# USB_PD.net
KiCad netlist of a schematic drawn in Altium Designer
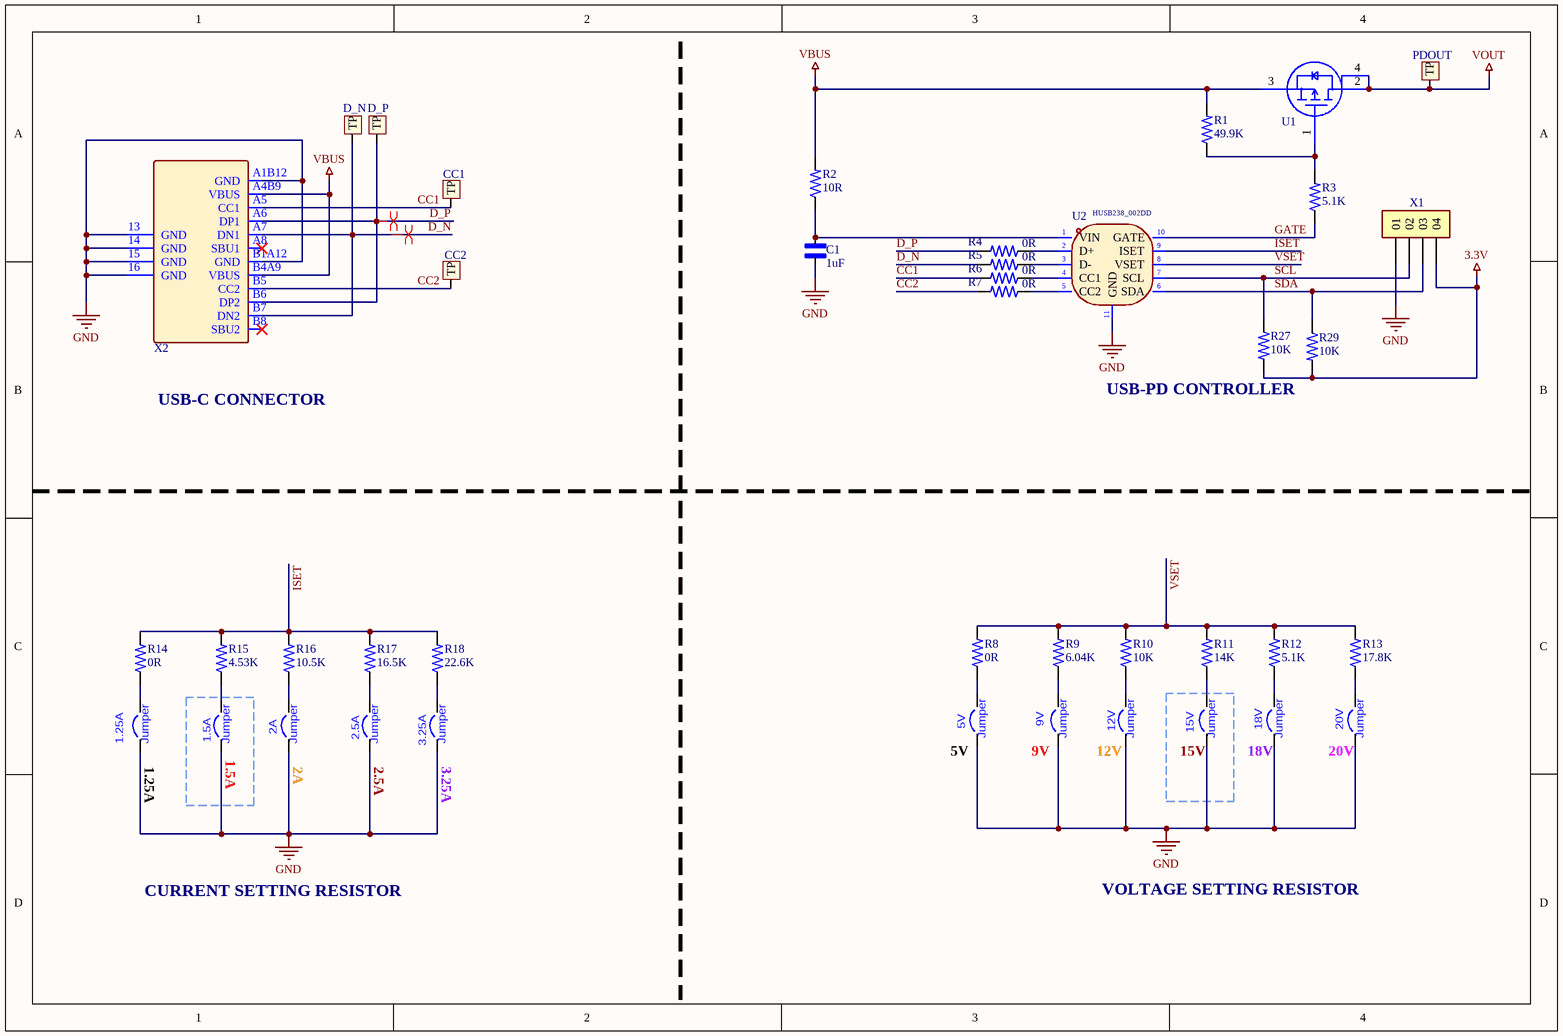
[diagram p0: USB_PD.SchDoc]

(export (version "E")
  (design (tool "Eeschema 10.0.6"))
  (components
    (comp (ref "1.5A")
      (value "Jumper")
      (footprint "PAD-JUMPER-2-NC_BY_PASTE_YES_SILK")
      (description "SMD JUMPER")
      (libsource (lib "USB_PD_DVD") (part "JUMPER SOLDER BRIDGE"))
    )
    (comp (ref "1.25A")
      (value "Jumper")
      (footprint "PAD-JUMPER-2-NC_BY_PASTE_YES_SILK")
      (description "SMD JUMPER")
      (libsource (lib "USB_PD_DVD") (part "JUMPER SOLDER BRIDGE"))
    )
    (comp (ref "2.5A")
      (value "Jumper")
      (footprint "PAD-JUMPER-2-NC_BY_PASTE_YES_SILK")
      (description "SMD JUMPER")
      (libsource (lib "USB_PD_DVD") (part "JUMPER SOLDER BRIDGE"))
    )
    (comp (ref "2A")
      (value "Jumper")
      (footprint "PAD-JUMPER-2-NC_BY_PASTE_YES_SILK")
      (description "SMD JUMPER")
      (libsource (lib "USB_PD_DVD") (part "JUMPER SOLDER BRIDGE"))
    )
    (comp (ref "3.25A")
      (value "Jumper")
      (footprint "PAD-JUMPER-2-NC_BY_PASTE_YES_SILK")
      (description "SMD JUMPER")
      (libsource (lib "USB_PD_DVD") (part "JUMPER SOLDER BRIDGE"))
    )
    (comp (ref "5V")
      (value "Jumper")
      (footprint "PAD-JUMPER-2-NC_BY_PASTE_YES_SILK")
      (description "SMD JUMPER")
      (libsource (lib "USB_PD_DVD") (part "JUMPER SOLDER BRIDGE"))
    )
    (comp (ref "9V")
      (value "Jumper")
      (footprint "PAD-JUMPER-2-NC_BY_PASTE_YES_SILK")
      (description "SMD JUMPER")
      (libsource (lib "USB_PD_DVD") (part "JUMPER SOLDER BRIDGE"))
    )
    (comp (ref "12V")
      (value "Jumper")
      (footprint "PAD-JUMPER-2-NC_BY_PASTE_YES_SILK")
      (description "SMD JUMPER")
      (libsource (lib "USB_PD_DVD") (part "JUMPER SOLDER BRIDGE"))
    )
    (comp (ref "15V")
      (value "Jumper")
      (footprint "PAD-JUMPER-2-NC_BY_PASTE_YES_SILK")
      (description "SMD JUMPER")
      (libsource (lib "USB_PD_DVD") (part "JUMPER SOLDER BRIDGE"))
    )
    (comp (ref "18V")
      (value "Jumper")
      (footprint "PAD-JUMPER-2-NC_BY_PASTE_YES_SILK")
      (description "SMD JUMPER")
      (libsource (lib "USB_PD_DVD") (part "JUMPER SOLDER BRIDGE"))
    )
    (comp (ref "20V")
      (value "Jumper")
      (footprint "PAD-JUMPER-2-NC_BY_PASTE_YES_SILK")
      (description "SMD JUMPER")
      (libsource (lib "USB_PD_DVD") (part "JUMPER SOLDER BRIDGE"))
    )
    (comp (ref "C1")
      (value "1uF")
      (footprint "CAP 0402")
      (fields
        (field (name "VOLTAGE") "50V")
        (field (name "TOLERANCE") "±10%")
        (field (name "Comment") "SMD capacitor")
      )
      (libsource (lib "USB_PD_DVD") (part "CAP_SMD_CERAMIC"))
    )
    (comp (ref "CC1")
      (value "TEST POINT")
      (footprint "TESTPOINT")
      (libsource (lib "USB_PD_DVD") (part "TEST POINT"))
    )
    (comp (ref "CC2")
      (value "TEST POINT")
      (footprint "TESTPOINT")
      (libsource (lib "USB_PD_DVD") (part "TEST POINT"))
    )
    (comp (ref "D_N")
      (value "TEST POINT")
      (footprint "TESTPOINT")
      (libsource (lib "USB_PD_DVD") (part "TEST POINT"))
    )
    (comp (ref "D_P")
      (value "TEST POINT")
      (footprint "TESTPOINT")
      (libsource (lib "USB_PD_DVD") (part "TEST POINT"))
    )
    (comp (ref "PDOUT")
      (value "TEST POINT")
      (footprint "TESTPOINT")
      (libsource (lib "USB_PD_DVD") (part "TEST POINT"))
    )
    (comp (ref "R1")
      (value "49.9K")
      (footprint "RES_0603")
      (fields (field (name "TOLERANCE") "±5%") (field (name "Comment") "SMD resistor"))
      (libsource (lib "USB_PD_DVD") (part "RES_SMD_CERAMIC"))
    )
    (comp (ref "R2")
      (value "10R")
      (footprint "RES_0603")
      (fields (field (name "TOLERANCE") "±5%") (field (name "Comment") "SMD resistor"))
      (libsource (lib "USB_PD_DVD") (part "RES_SMD_CERAMIC"))
    )
    (comp (ref "R3")
      (value "5.1K")
      (footprint "RES_0603")
      (fields (field (name "TOLERANCE") "±5%") (field (name "Comment") "SMD resistor"))
      (libsource (lib "USB_PD_DVD") (part "RES_SMD_CERAMIC"))
    )
    (comp (ref "R4")
      (value "0R")
      (footprint "RES 0402")
      (fields (field (name "TOLERANCE") "±5%") (field (name "Comment") "SMD resistor"))
      (libsource (lib "USB_PD_DVD") (part "RES_SMD_CERAMIC"))
    )
    (comp (ref "R5")
      (value "0R")
      (footprint "RES 0402")
      (fields (field (name "TOLERANCE") "±5%") (field (name "Comment") "SMD resistor"))
      (libsource (lib "USB_PD_DVD") (part "RES_SMD_CERAMIC"))
    )
    (comp (ref "R6")
      (value "0R")
      (footprint "RES 0402")
      (fields (field (name "TOLERANCE") "±5%") (field (name "Comment") "SMD resistor"))
      (libsource (lib "USB_PD_DVD") (part "RES_SMD_CERAMIC"))
    )
    (comp (ref "R7")
      (value "0R")
      (footprint "RES 0402")
      (fields (field (name "TOLERANCE") "±5%") (field (name "Comment") "SMD resistor"))
      (libsource (lib "USB_PD_DVD") (part "RES_SMD_CERAMIC"))
    )
    (comp (ref "R8")
      (value "0R")
      (footprint "RES 0402")
      (fields (field (name "TOLERANCE") "±5%") (field (name "Comment") "SMD resistor"))
      (libsource (lib "USB_PD_DVD") (part "RES_SMD_CERAMIC"))
    )
    (comp (ref "R9")
      (value "6.04K")
      (footprint "RES 0402")
      (fields (field (name "TOLERANCE") "±5%") (field (name "Comment") "SMD resistor"))
      (libsource (lib "USB_PD_DVD") (part "RES_SMD_CERAMIC"))
    )
    (comp (ref "R10")
      (value "10K")
      (footprint "RES 0402")
      (fields (field (name "TOLERANCE") "±5%") (field (name "Comment") "SMD resistor"))
      (libsource (lib "USB_PD_DVD") (part "RES_SMD_CERAMIC"))
    )
    (comp (ref "R11")
      (value "14K")
      (footprint "RES 0402")
      (fields (field (name "TOLERANCE") "±5%") (field (name "Comment") "SMD resistor"))
      (libsource (lib "USB_PD_DVD") (part "RES_SMD_CERAMIC"))
    )
    (comp (ref "R12")
      (value "5.1K")
      (footprint "RES 0402")
      (fields (field (name "TOLERANCE") "±5%") (field (name "Comment") "SMD resistor"))
      (libsource (lib "USB_PD_DVD") (part "RES_SMD_CERAMIC"))
    )
    (comp (ref "R13")
      (value "17.8K")
      (footprint "RES 0402")
      (fields (field (name "TOLERANCE") "±5%") (field (name "Comment") "SMD resistor"))
      (libsource (lib "USB_PD_DVD") (part "RES_SMD_CERAMIC"))
    )
    (comp (ref "R14")
      (value "0R")
      (footprint "RES 0402")
      (fields (field (name "TOLERANCE") "±5%") (field (name "Comment") "SMD resistor"))
      (libsource (lib "USB_PD_DVD") (part "RES_SMD_CERAMIC"))
    )
    (comp (ref "R15")
      (value "4.53K")
      (footprint "RES 0402")
      (fields (field (name "TOLERANCE") "±5%") (field (name "Comment") "SMD resistor"))
      (libsource (lib "USB_PD_DVD") (part "RES_SMD_CERAMIC"))
    )
    (comp (ref "R16")
      (value "10.5K")
      (footprint "RES 0402")
      (fields (field (name "TOLERANCE") "±5%") (field (name "Comment") "SMD resistor"))
      (libsource (lib "USB_PD_DVD") (part "RES_SMD_CERAMIC"))
    )
    (comp (ref "R17")
      (value "16.5K")
      (footprint "RES 0402")
      (fields (field (name "TOLERANCE") "±5%") (field (name "Comment") "SMD resistor"))
      (libsource (lib "USB_PD_DVD") (part "RES_SMD_CERAMIC"))
    )
    (comp (ref "R18")
      (value "22.6K")
      (footprint "RES 0402")
      (fields (field (name "TOLERANCE") "±5%") (field (name "Comment") "SMD resistor"))
      (libsource (lib "USB_PD_DVD") (part "RES_SMD_CERAMIC"))
    )
    (comp (ref "R27")
      (value "10K")
      (footprint "RES 0402")
      (fields (field (name "TOLERANCE") "±5%") (field (name "Comment") "SMD resistor NC"))
      (libsource (lib "USB_PD_DVD") (part "RES_SMD_CERAMIC"))
    )
    (comp (ref "R29")
      (value "10K")
      (footprint "RES 0402")
      (fields (field (name "TOLERANCE") "±5%") (field (name "Comment") "SMD resistor NC"))
      (libsource (lib "USB_PD_DVD") (part "RES_SMD_CERAMIC"))
    )
    (comp (ref "U1")
      (value "P-Channel  MOSFET")
      (footprint "SOT-223-4_L6.5-W3.5-P2.30-LS7.0-BR")
      (description "60V 7A 2W 35mΩ@4.5V,4A 3V@250uA 1 P-Channel SOT-223 MOSFETs ROHS")
      (fields
        (field (name "MANIFACTURING PART NUMBER") "DMP6023LE-13")
        (field (name "JLCPCB PART #") "C154901")
      )
      (libsource (lib "USB_PD_DVD") (part "DMP6023LE-13"))
    )
    (comp (ref "U2")
      (value "HUSB238_002DD")
      (footprint "DFN-10")
      (description "DFN-10L(3x3) USB Converters ROHS")
      (fields (field (name "JLCPCB PART #") "C7471904") (field (name "Comment") "USB-PD-IC"))
      (libsource (lib "USB_PD_DVD") (part "USB_PD_HUSB238"))
    )
    (comp (ref "X1")
      (value "Header X 5")
      (footprint "SAMTEC_TS-104-T-A")
      (description "4 pin header pitch 2.54mm")
      (fields (field (name "MANIFACTURING PART NUMBER") "C91552"))
      (libsource (lib "USB_PD_DVD") (part "4 Pin Header"))
    )
    (comp (ref "X2")
      (value "USB-C connector")
      (footprint "USB-C-SMD_TYPEC-304J-BCP16")
      (description "5A USB 3.1 1 Surface Mount, Right Angle 16P Female -40℃~+85℃ Type-C SMD USB Connectors ROHS")
      (fields
        (field (name "MANIFACTURING PART NUMBER") "TYPEC-304J-BCP16")
        (field (name "JLCPCB PART #") "C2835315")
      )
      (libsource (lib "USB_PD_DVD") (part "TYPEC-304J-BCP16"))
    )
  )
  (nets
    (net (code "1") (name "/CC1") (class "Default")
      (node (ref "CC1") (pin "1") (pinfunction "TP_1") (pintype "passive"))
      (node (ref "R6") (pin "2") (pinfunction "2_2") (pintype "passive"))
      (node (ref "X2") (pin "A5") (pinfunction "CC1_A5") (pintype "passive"))
    )
    (net (code "2") (name "/CC2") (class "Default")
      (node (ref "CC2") (pin "1") (pinfunction "TP_1") (pintype "passive"))
      (node (ref "R7") (pin "2") (pinfunction "2_2") (pintype "passive"))
      (node (ref "X2") (pin "B5") (pinfunction "CC2_B5") (pintype "passive"))
    )
    (net (code "3") (name "/D_N") (class "Default")
      (node (ref "D_N") (pin "1") (pinfunction "TP_1") (pintype "passive"))
      (node (ref "R5") (pin "2") (pinfunction "2_2") (pintype "passive"))
      (node (ref "X2") (pin "A7") (pinfunction "DN1_A7") (pintype "passive"))
      (node (ref "X2") (pin "B7") (pinfunction "DN2_B7") (pintype "passive"))
    )
    (net (code "4") (name "/D_P") (class "Default")
      (node (ref "D_P") (pin "1") (pinfunction "TP_1") (pintype "passive"))
      (node (ref "R4") (pin "2") (pinfunction "2_2") (pintype "passive"))
      (node (ref "X2") (pin "A6") (pinfunction "DP1_A6") (pintype "passive"))
      (node (ref "X2") (pin "B6") (pinfunction "DP2_B6") (pintype "passive"))
    )
    (net (code "5") (name "/GATE") (class "Default")
      (node (ref "R3") (pin "1") (pinfunction "1_1") (pintype "passive"))
      (node (ref "U2") (pin "10") (pinfunction "GATE_10") (pintype "passive"))
    )
    (net (code "6") (name "/ISET") (class "Default")
      (node (ref "R14") (pin "2") (pinfunction "2_2") (pintype "passive"))
      (node (ref "R15") (pin "2") (pinfunction "2_2") (pintype "passive"))
      (node (ref "R16") (pin "2") (pinfunction "2_2") (pintype "passive"))
      (node (ref "R17") (pin "2") (pinfunction "2_2") (pintype "passive"))
      (node (ref "R18") (pin "2") (pinfunction "2_2") (pintype "passive"))
      (node (ref "U2") (pin "9") (pinfunction "ISET_9") (pintype "passive"))
    )
    (net (code "7") (name "/SCL") (class "Default")
      (node (ref "R27") (pin "1") (pinfunction "1_1") (pintype "passive"))
      (node (ref "U2") (pin "7") (pinfunction "SCL_7") (pintype "passive"))
      (node (ref "X1") (pin "02") (pinfunction "02_02") (pintype "passive"))
    )
    (net (code "8") (name "/SDA") (class "Default")
      (node (ref "R29") (pin "1") (pinfunction "1_1") (pintype "passive"))
      (node (ref "U2") (pin "6") (pinfunction "SDA_6") (pintype "passive"))
      (node (ref "X1") (pin "03") (pinfunction "03_03") (pintype "passive"))
    )
    (net (code "9") (name "/VSET") (class "Default")
      (node (ref "R10") (pin "2") (pinfunction "2_2") (pintype "passive"))
      (node (ref "R11") (pin "2") (pinfunction "2_2") (pintype "passive"))
      (node (ref "R12") (pin "2") (pinfunction "2_2") (pintype "passive"))
      (node (ref "R13") (pin "2") (pinfunction "2_2") (pintype "passive"))
      (node (ref "R8") (pin "2") (pinfunction "2_2") (pintype "passive"))
      (node (ref "R9") (pin "2") (pinfunction "2_2") (pintype "passive"))
      (node (ref "U2") (pin "8") (pinfunction "VSET_8") (pintype "passive"))
    )
    (net (code "10") (name "3.3V") (class "Default")
      (node (ref "R27") (pin "2") (pinfunction "2_2") (pintype "passive"))
      (node (ref "R29") (pin "2") (pinfunction "2_2") (pintype "passive"))
      (node (ref "X1") (pin "04") (pinfunction "04_04") (pintype "passive"))
    )
    (net (code "11") (name "GND") (class "Default")
      (node (ref "1.25A") (pin "1") (pinfunction "1_1") (pintype "passive"))
      (node (ref "1.5A") (pin "1") (pinfunction "1_1") (pintype "passive"))
      (node (ref "12V") (pin "1") (pinfunction "1_1") (pintype "passive"))
      (node (ref "15V") (pin "1") (pinfunction "1_1") (pintype "passive"))
      (node (ref "18V") (pin "1") (pinfunction "1_1") (pintype "passive"))
      (node (ref "2.5A") (pin "1") (pinfunction "1_1") (pintype "passive"))
      (node (ref "20V") (pin "1") (pinfunction "1_1") (pintype "passive"))
      (node (ref "2A") (pin "1") (pinfunction "1_1") (pintype "passive"))
      (node (ref "3.25A") (pin "1") (pinfunction "1_1") (pintype "passive"))
      (node (ref "5V") (pin "1") (pinfunction "1_1") (pintype "passive"))
      (node (ref "9V") (pin "1") (pinfunction "1_1") (pintype "passive"))
      (node (ref "C1") (pin "2") (pinfunction "2_2") (pintype "passive"))
      (node (ref "U2") (pin "11") (pinfunction "GND_11") (pintype "passive"))
      (node (ref "X1") (pin "01") (pinfunction "01_01") (pintype "passive"))
      (node (ref "X2") (pin "13") (pinfunction "GND_13") (pintype "passive"))
      (node (ref "X2") (pin "14") (pinfunction "GND_14") (pintype "passive"))
      (node (ref "X2") (pin "15") (pinfunction "GND_15") (pintype "passive"))
      (node (ref "X2") (pin "16") (pinfunction "GND_16") (pintype "passive"))
      (node (ref "X2") (pin "A1B12") (pinfunction "GND_A1B12") (pintype "passive"))
      (node (ref "X2") (pin "B1A12") (pinfunction "GND_B1A12") (pintype "passive"))
    )
    (net (code "12") (name "Net-(1.5A-Pad2)") (class "Default")
      (node (ref "1.5A") (pin "2") (pinfunction "2_2") (pintype "passive"))
      (node (ref "R15") (pin "1") (pinfunction "1_1") (pintype "passive"))
    )
    (net (code "13") (name "Net-(1.25A-Pad2)") (class "Default")
      (node (ref "1.25A") (pin "2") (pinfunction "2_2") (pintype "passive"))
      (node (ref "R14") (pin "1") (pinfunction "1_1") (pintype "passive"))
    )
    (net (code "14") (name "Net-(2.5A-Pad2)") (class "Default")
      (node (ref "2.5A") (pin "2") (pinfunction "2_2") (pintype "passive"))
      (node (ref "R17") (pin "1") (pinfunction "1_1") (pintype "passive"))
    )
    (net (code "15") (name "Net-(2A-Pad2)") (class "Default")
      (node (ref "2A") (pin "2") (pinfunction "2_2") (pintype "passive"))
      (node (ref "R16") (pin "1") (pinfunction "1_1") (pintype "passive"))
    )
    (net (code "16") (name "Net-(3.25A-Pad2)") (class "Default")
      (node (ref "3.25A") (pin "2") (pinfunction "2_2") (pintype "passive"))
      (node (ref "R18") (pin "1") (pinfunction "1_1") (pintype "passive"))
    )
    (net (code "17") (name "Net-(5V-Pad2)") (class "Default")
      (node (ref "5V") (pin "2") (pinfunction "2_2") (pintype "passive"))
      (node (ref "R8") (pin "1") (pinfunction "1_1") (pintype "passive"))
    )
    (net (code "18") (name "Net-(9V-Pad2)") (class "Default")
      (node (ref "9V") (pin "2") (pinfunction "2_2") (pintype "passive"))
      (node (ref "R9") (pin "1") (pinfunction "1_1") (pintype "passive"))
    )
    (net (code "19") (name "Net-(12V-Pad2)") (class "Default")
      (node (ref "12V") (pin "2") (pinfunction "2_2") (pintype "passive"))
      (node (ref "R10") (pin "1") (pinfunction "1_1") (pintype "passive"))
    )
    (net (code "20") (name "Net-(15V-Pad2)") (class "Default")
      (node (ref "15V") (pin "2") (pinfunction "2_2") (pintype "passive"))
      (node (ref "R11") (pin "1") (pinfunction "1_1") (pintype "passive"))
    )
    (net (code "21") (name "Net-(18V-Pad2)") (class "Default")
      (node (ref "18V") (pin "2") (pinfunction "2_2") (pintype "passive"))
      (node (ref "R12") (pin "1") (pinfunction "1_1") (pintype "passive"))
    )
    (net (code "22") (name "Net-(20V-Pad2)") (class "Default")
      (node (ref "20V") (pin "2") (pinfunction "2_2") (pintype "passive"))
      (node (ref "R13") (pin "1") (pinfunction "1_1") (pintype "passive"))
    )
    (net (code "23") (name "Net-(U1-G)") (class "Default")
      (node (ref "R1") (pin "1") (pinfunction "1_1") (pintype "passive"))
      (node (ref "R3") (pin "2") (pinfunction "2_2") (pintype "passive"))
      (node (ref "U1") (pin "1") (pinfunction "G_1") (pintype "passive"))
    )
    (net (code "24") (name "Net-(U2-CC1)") (class "Default")
      (node (ref "R6") (pin "1") (pinfunction "1_1") (pintype "passive"))
      (node (ref "U2") (pin "4") (pinfunction "CC1_4") (pintype "passive"))
    )
    (net (code "25") (name "Net-(U2-CC2)") (class "Default")
      (node (ref "R7") (pin "1") (pinfunction "1_1") (pintype "passive"))
      (node (ref "U2") (pin "5") (pinfunction "CC2_5") (pintype "passive"))
    )
    (net (code "26") (name "Net-(U2-D+)") (class "Default")
      (node (ref "R4") (pin "1") (pinfunction "1_1") (pintype "passive"))
      (node (ref "U2") (pin "2") (pinfunction "D+_2") (pintype "passive"))
    )
    (net (code "27") (name "Net-(U2-D-)") (class "Default")
      (node (ref "R5") (pin "1") (pinfunction "1_1") (pintype "passive"))
      (node (ref "U2") (pin "3") (pinfunction "D-_3") (pintype "passive"))
    )
    (net (code "28") (name "Net-(U2-VIN)") (class "Default")
      (node (ref "C1") (pin "1") (pinfunction "1_1") (pintype "passive"))
      (node (ref "R2") (pin "1") (pinfunction "1_1") (pintype "passive"))
      (node (ref "U2") (pin "1") (pinfunction "VIN_1") (pintype "passive"))
    )
    (net (code "29") (name "VBUS") (class "Default")
      (node (ref "R1") (pin "2") (pinfunction "2_2") (pintype "passive"))
      (node (ref "R2") (pin "2") (pinfunction "2_2") (pintype "passive"))
      (node (ref "U1") (pin "3") (pinfunction "S_3") (pintype "passive"))
      (node (ref "X2") (pin "A4B9") (pinfunction "VBUS_A4B9") (pintype "passive"))
      (node (ref "X2") (pin "B4A9") (pinfunction "VBUS_B4A9") (pintype "passive"))
    )
    (net (code "30") (name "VOUT") (class "Default")
      (node (ref "PDOUT") (pin "1") (pinfunction "TP_1") (pintype "passive"))
      (node (ref "U1") (pin "2") (pinfunction "D_2") (pintype "passive"))
      (node (ref "U1") (pin "4") (pinfunction "D_4") (pintype "passive"))
    )
    (net (code "31") (name "unconnected-(X2-SBU1-PadA8)") (class "Default")
      (node (ref "X2") (pin "A8") (pinfunction "SBU1_A8") (pintype "passive+no_connect"))
    )
    (net (code "32") (name "unconnected-(X2-SBU2-PadB8)") (class "Default")
      (node (ref "X2") (pin "B8") (pinfunction "SBU2_B8") (pintype "passive+no_connect"))
    )
  )
)
